# Power_Management.net
KiCad netlist of a schematic drawn in Altium Designer
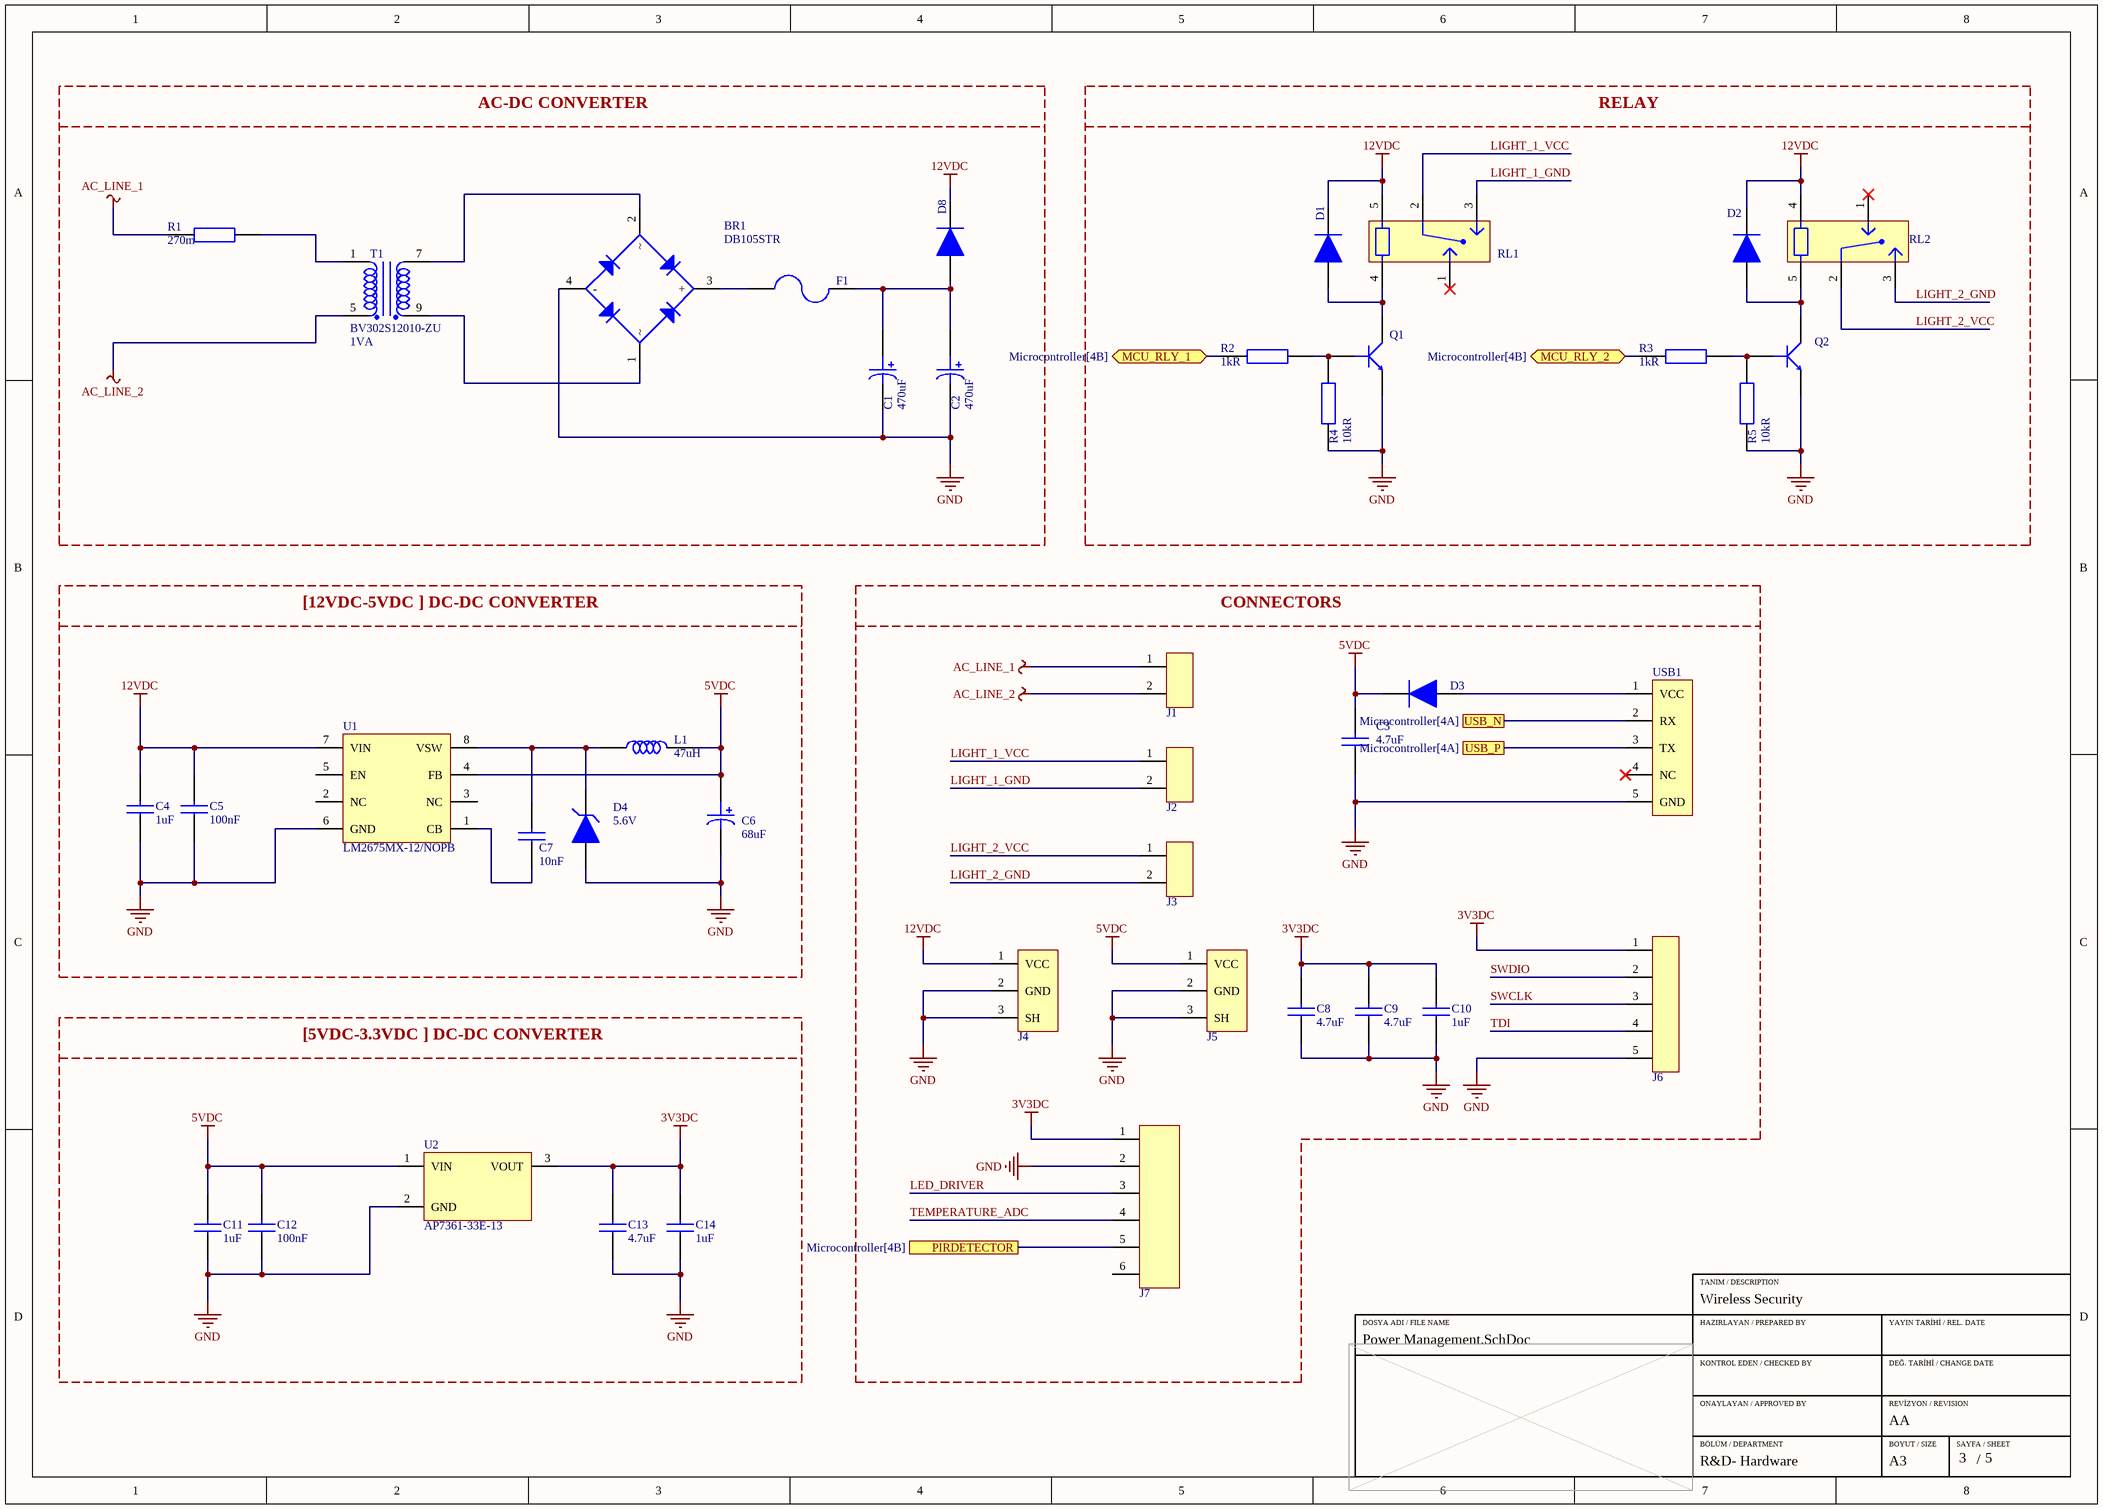
[diagram p0: Power Management.SchDoc]

(export (version "E")
  (design (tool "Eeschema 10.0.6"))
  (components
    (comp (ref "BR1")
      (value "DB105STR")
      (footprint "DB105STR")
      (description "Bridge Diode AC-DC")
      (fields
        (field (name "MANUFACTURER") "Sangdest Microelectronics")
        (field (name "DESIGNED BY") "Cem Uğurcan Özdemir")
      )
      (libsource (lib "UDEMY_Library") (part "DB105STR"))
    )
    (comp (ref "C1")
      (value "ESH477M050AH4AA")
      (footprint "CAP_RADIAL_D10_P5")
      (description "CAP ALU ELEC 470uF 50V RADIAL")
      (fields
        (field (name "MANUFACTURER") "KEMET")
        (field (name "TOLERANCE") "20%")
        (field (name "CAPACITANCE") "470uF")
        (field (name "DESIGNED BY") "Cem Uğurcan Özdemir")
      )
      (libsource (lib "UDEMY_Library") (part "CAP ALU ELEC 470uF 50V"))
    )
    (comp (ref "C2")
      (value "ESH477M050AH4AA")
      (footprint "CAP_RADIAL_D10_P5")
      (description "CAP ALU ELEC 470uF 50V RADIAL")
      (fields
        (field (name "MANUFACTURER") "KEMET")
        (field (name "TOLERANCE") "20%")
        (field (name "CAPACITANCE") "470uF")
        (field (name "DESIGNED BY") "Cem Uğurcan Özdemir")
      )
      (libsource (lib "UDEMY_Library") (part "CAP ALU ELEC 470uF 50V"))
    )
    (comp (ref "C3")
      (value "CL21A475KAQNNNE")
      (footprint "CAP_0805")
      (description "CAP CER 4.7uF %10 0805")
      (fields
        (field (name "MANUFACTURER") "Samsung")
        (field (name "TOLERANCE") "10%")
        (field (name "CAPACITANCE") "4.7uF")
        (field (name "DESIGNED BY") "Cem Uğurcan Özdemir")
      )
      (libsource (lib "UDEMY_Library") (part "CAP CER 4.7uF 0805"))
    )
    (comp (ref "C4")
      (value "CL21B105KBFNNNE")
      (footprint "CAP_0805")
      (description "CAP CER 1uF %10 0805")
      (fields
        (field (name "MANUFACTURER") "Samsung")
        (field (name "TOLERANCE") "10%")
        (field (name "CAPACITANCE") "1uF")
        (field (name "DESIGNED BY") "Cem Uğurcan Özdemir")
      )
      (libsource (lib "UDEMY_Library") (part "CAP CER 1uF 0805"))
    )
    (comp (ref "C5")
      (value "CL21B104KBCNNNC")
      (footprint "CAP_0805")
      (description "CAP CER 100nF %10 0805")
      (fields
        (field (name "MANUFACTURER") "Samsung")
        (field (name "TOLERANCE") "10%")
        (field (name "CAPACITANCE") "100nF")
        (field (name "DESIGNED BY") "Cem Uğurcan Özdemir")
      )
      (libsource (lib "UDEMY_Library") (part "CAP CER 100nF 0805"))
    )
    (comp (ref "C6")
      (value "EEV686M035A9HAA")
      (footprint "CAP_EEVseries")
      (description "Cap Aluminum Lytic 68uF 35V 20% (6.3 X 7.7mm) SMD 280mA 2000h 105C T/R")
      (fields
        (field (name "MANUFACTURER") "KEMET")
        (field (name "TOLERANCE") "20%")
        (field (name "CAPACITANCE") "68uF")
        (field (name "DESIGNED BY") "Cem Uğurcan Özdemir")
      )
      (libsource (lib "UDEMY_Library") (part "CAP ALU 68uF"))
    )
    (comp (ref "C7")
      (value "0603B103K160CT")
      (footprint "CAP_0603")
      (description "CAP CER 10nF %10 0603")
      (fields
        (field (name "MANUFACTURER") "Walsin Technologies")
        (field (name "TOLERANCE") "10%")
        (field (name "CAPACITANCE") "10nF")
        (field (name "DESIGNED BY") "Cem Uğurcan Özdemir")
      )
      (libsource (lib "UDEMY_Library") (part "CAP CER 10nF 0603"))
    )
    (comp (ref "C8")
      (value "CL21A475KAQNNNE")
      (footprint "CAP_0805")
      (description "CAP CER 4.7uF %10 0805")
      (fields
        (field (name "MANUFACTURER") "Samsung")
        (field (name "TOLERANCE") "10%")
        (field (name "CAPACITANCE") "4.7uF")
        (field (name "DESIGNED BY") "Cem Uğurcan Özdemir")
      )
      (libsource (lib "UDEMY_Library") (part "CAP CER 4.7uF 0805"))
    )
    (comp (ref "C9")
      (value "CL21A475KAQNNNE")
      (footprint "CAP_0805")
      (description "CAP CER 4.7uF %10 0805")
      (fields
        (field (name "MANUFACTURER") "Samsung")
        (field (name "TOLERANCE") "10%")
        (field (name "CAPACITANCE") "4.7uF")
        (field (name "DESIGNED BY") "Cem Uğurcan Özdemir")
      )
      (libsource (lib "UDEMY_Library") (part "CAP CER 4.7uF 0805"))
    )
    (comp (ref "C10")
      (value "CL21B105KBFNNNE")
      (footprint "CAP_0805")
      (description "CAP CER 1uF %10 0805")
      (fields
        (field (name "MANUFACTURER") "Samsung")
        (field (name "TOLERANCE") "10%")
        (field (name "CAPACITANCE") "1uF")
        (field (name "DESIGNED BY") "Cem Uğurcan Özdemir")
      )
      (libsource (lib "UDEMY_Library") (part "CAP CER 1uF 0805"))
    )
    (comp (ref "C11")
      (value "CL21B105KBFNNNE")
      (footprint "CAP_0805")
      (description "CAP CER 1uF %10 0805")
      (fields
        (field (name "MANUFACTURER") "Samsung")
        (field (name "TOLERANCE") "10%")
        (field (name "CAPACITANCE") "1uF")
        (field (name "DESIGNED BY") "Cem Uğurcan Özdemir")
      )
      (libsource (lib "UDEMY_Library") (part "CAP CER 1uF 0805"))
    )
    (comp (ref "C12")
      (value "C0603C104K5RACTU")
      (footprint "CAP_0603")
      (description "CAP CER 100nF %10 0603 SMD")
      (fields
        (field (name "MANUFACTURER") "KEMET")
        (field (name "TOLERANCE") "10%")
        (field (name "CAPACITANCE") "100nF")
        (field (name "DESIGNED BY") "Cem Uğurcan Özdemir")
      )
      (libsource (lib "UDEMY_Library") (part "CAP CER 100nF 0603"))
    )
    (comp (ref "C13")
      (value "CL21A475KAQNNNE")
      (footprint "CAP_0805")
      (description "CAP CER 4.7uF %10 0805")
      (fields
        (field (name "MANUFACTURER") "Samsung")
        (field (name "TOLERANCE") "10%")
        (field (name "CAPACITANCE") "4.7uF")
        (field (name "DESIGNED BY") "Cem Uğurcan Özdemir")
      )
      (libsource (lib "UDEMY_Library") (part "CAP CER 4.7uF 0805"))
    )
    (comp (ref "C14")
      (value "CL21B105KBFNNNE")
      (footprint "CAP_0805")
      (description "CAP CER 1uF %10 0805")
      (fields
        (field (name "MANUFACTURER") "Samsung")
        (field (name "TOLERANCE") "10%")
        (field (name "CAPACITANCE") "1uF")
        (field (name "DESIGNED BY") "Cem Uğurcan Özdemir")
      )
      (libsource (lib "UDEMY_Library") (part "CAP CER 1uF 0805"))
    )
    (comp (ref "D1")
      (value "1N4148WS")
      (footprint "SOD323F")
      (description "Diode, Single, 75 V, 150 mA, 1 V, 4 ns")
      (fields
        (field (name "MANUFACTURER") "ON Semiconductor / Fairchild")
        (field (name "DESIGNED BY") "Cem Uğurcan Özdemir")
      )
      (libsource (lib "UDEMY_Library") (part "1N4148WS"))
    )
    (comp (ref "D2")
      (value "1N4148WS")
      (footprint "SOD323F")
      (description "Diode, Single, 75 V, 150 mA, 1 V, 4 ns")
      (fields
        (field (name "MANUFACTURER") "ON Semiconductor / Fairchild")
        (field (name "DESIGNED BY") "Cem Uğurcan Özdemir")
      )
      (libsource (lib "UDEMY_Library") (part "1N4148WS"))
    )
    (comp (ref "D3")
      (value "1N4148WS")
      (footprint "SOD323F")
      (description "Diode, Single, 75 V, 150 mA, 1 V, 4 ns")
      (fields
        (field (name "MANUFACTURER") "ON Semiconductor / Fairchild")
        (field (name "DESIGNED BY") "Cem Uğurcan Özdemir")
      )
      (libsource (lib "UDEMY_Library") (part "1N4148WS"))
    )
    (comp (ref "D4")
      (value "1SMB5919BT3G")
      (footprint "SMB")
      (description "Diode Zener Single 5.6V 5% 3W 2-Pin SMB T/R")
      (fields
        (field (name "MANUFACTURER") "ON Semiconductor")
        (field (name "TOLERANCE") "5%")
        (field (name "WORKING VOLTAGE") "5.6V")
        (field (name "DESIGNED BY") "Cem Uğurcan Özdemir")
      )
      (libsource (lib "UDEMY_Library") (part "1SMB5919BT3G"))
    )
    (comp (ref "D8")
      (value "1N4148WS")
      (footprint "SOD323F")
      (description "Diode, Single, 75 V, 150 mA, 1 V, 4 ns")
      (fields
        (field (name "MANUFACTURER") "ON Semiconductor / Fairchild")
        (field (name "DESIGNED BY") "Cem Uğurcan Özdemir")
      )
      (libsource (lib "UDEMY_Library") (part "1N4148WS"))
    )
    (comp (ref "F1")
      (value "3413.0216.22")
      (footprint "3413.0216.22")
      (description "FUSE BRD MNT 1A 32VAC 63VDC 1206")
      (fields (field (name "MANUFACTURER") "Schurter") (field (name "DESIGNED BY") "Cem Uğurcan Özdemir"))
      (libsource (lib "UDEMY_Library") (part "FUSE 3413.0216.22"))
    )
    (comp (ref "J1")
      (value "TBP01R1-508-02BE")
      (footprint "TBP01R1-508")
      (description "Conn Shrouded Header HDR 2 POS 5.08mm Solder RA Side Entry Thru-Hole Bag")
      (fields (field (name "MANUFACTURER") "CUI") (field (name "DESIGNED BY") "Cem Uğurcan Özdemir"))
      (libsource (lib "UDEMY_Library") (part "TBP01R1-508-02BE"))
    )
    (comp (ref "J2")
      (value "TBP01R1-508-02BE")
      (footprint "TBP01R1-508")
      (description "Conn Shrouded Header HDR 2 POS 5.08mm Solder RA Side Entry Thru-Hole Bag")
      (fields (field (name "MANUFACTURER") "CUI") (field (name "DESIGNED BY") "Cem Uğurcan Özdemir"))
      (libsource (lib "UDEMY_Library") (part "TBP01R1-508-02BE"))
    )
    (comp (ref "J3")
      (value "TBP01R1-508-02BE")
      (footprint "TBP01R1-508")
      (description "Conn Shrouded Header HDR 2 POS 5.08mm Solder RA Side Entry Thru-Hole Bag")
      (fields (field (name "MANUFACTURER") "CUI") (field (name "DESIGNED BY") "Cem Uğurcan Özdemir"))
      (libsource (lib "UDEMY_Library") (part "TBP01R1-508-02BE"))
    )
    (comp (ref "J4")
      (value "PJ-037AH-SMT-TR")
      (footprint "JACK")
      (description "DC Power Connectors Power Jacks")
      (fields (field (name "MANUFACTURER") "CUI") (field (name "DESIGNED BY") "Cem Uğurcan Özdemir"))
      (libsource (lib "UDEMY_Library") (part "PJ-037AH-SMT-TR"))
    )
    (comp (ref "J5")
      (value "PJ-037AH-SMT-TR")
      (footprint "JACK")
      (description "DC Power Connectors Power Jacks")
      (fields (field (name "MANUFACTURER") "CUI") (field (name "DESIGNED BY") "Cem Uğurcan Özdemir"))
      (libsource (lib "UDEMY_Library") (part "PJ-037AH-SMT-TR"))
    )
    (comp (ref "J6")
      (value "SMH-105-02-L-S")
      (footprint "PINHEADER1X5_RA")
      (description ".100 C.L. HORIZONTAL SMT SOCKET")
      (fields (field (name "MANUFACTURER") "Samtec") (field (name "DESIGNED BY") "Cem Uğurcan Özdemir"))
      (libsource (lib "UDEMY_Library") (part "SMH-105-02-L-S"))
    )
    (comp (ref "J7")
      (value "64800611622")
      (footprint "64800611622")
      (description "1.50mm 6PIN Connector")
      (fields
        (field (name "MANUFACTURER") "Wurth Electronics")
        (field (name "DESIGNED BY") "Cem Uğurcan Özdemir")
      )
      (libsource (lib "UDEMY_Library") (part "64800611622_conn_6pin"))
    )
    (comp (ref "L1")
      (value "78438335470")
      (footprint "IND_1212")
      (description "FIXED IND 47UH 390MA 2.3 OHM SMD")
      (fields
        (field (name "MANUFACTURER") "Wurth Electronics")
        (field (name "TOLERANCE") "30%")
        (field (name "INDUCTANCE") "47uH")
        (field (name "DESIGNED BY") "Cem Uğurcan Özdemir")
      )
      (libsource (lib "UDEMY_Library") (part "IND 47uH"))
    )
    (comp (ref "Q1")
      (value "MMBT3904-7-F")
      (footprint "SOT-23F")
      (description "Transistor General Purpose BJT NPN 40 Volt 0.2A Automotive 3-Pin SOT-23")
      (fields (field (name "MANUFACTURER") "Diodes Zetex") (field (name "DESIGNED BY") "Cem Uğurcan Özdemir"))
      (libsource (lib "UDEMY_Library") (part "MMBT3904-7-F"))
    )
    (comp (ref "Q2")
      (value "MMBT3904-7-F")
      (footprint "SOT-23F")
      (description "Transistor General Purpose BJT NPN 40 Volt 0.2A Automotive 3-Pin SOT-23")
      (fields (field (name "MANUFACTURER") "Diodes Zetex") (field (name "DESIGNED BY") "Cem Uğurcan Özdemir"))
      (libsource (lib "UDEMY_Library") (part "MMBT3904-7-F"))
    )
    (comp (ref "R1")
      (value "5WD27")
      (footprint "RES_AXIAL_W")
      (description "Resistor 5 Watt Cermet Wirewound Flameproof .27 Ohm 5% Axial Lead")
      (fields
        (field (name "MANUFACTURER") "NTE Electronics")
        (field (name "TOLERANCE") "5%")
        (field (name "RESISTANCE") "270m")
        (field (name "DESIGNED BY") "Cem Uğurcan Özdemir")
      )
      (libsource (lib "CourseProjectLibrary") (part "5WD27"))
    )
    (comp (ref "R2")
      (value "RC0603FR-0710KL")
      (footprint "RES_0603")
      (description "RES 1K %1 OHM 0603 SMD")
      (fields
        (field (name "MANUFACTURER") "Yageo")
        (field (name "MANUFACTURER PART NUMBER") "RC0603JR-071KL")
        (field (name "RESISTANCE") "1kR")
        (field (name "DESIGNED BY") "Cem Uğurcan Özdemir")
      )
      (libsource (lib "UDEMY_Library") (part "RES 1K OHM 0603"))
    )
    (comp (ref "R3")
      (value "RC0603FR-0710KL")
      (footprint "RES_0603")
      (description "RES 1K %1 OHM 0603 SMD")
      (fields
        (field (name "MANUFACTURER") "Yageo")
        (field (name "MANUFACTURER PART NUMBER") "RC0603JR-071KL")
        (field (name "RESISTANCE") "1kR")
        (field (name "DESIGNED BY") "Cem Uğurcan Özdemir")
      )
      (libsource (lib "UDEMY_Library") (part "RES 1K OHM 0603"))
    )
    (comp (ref "R4")
      (value "RC0603FR-0710KL")
      (footprint "RES_0603")
      (description "RES 10K %1 OHM 0603 SMD")
      (fields
        (field (name "MANUFACTURER") "Yageo")
        (field (name "TOLERANCE") "1%")
        (field (name "RESISTANCE") "10kR")
        (field (name "DESIGNED BY") "Cem Uğurcan Özdemir")
      )
      (libsource (lib "UDEMY_Library") (part "RES 10K OHM 0603"))
    )
    (comp (ref "R5")
      (value "RC0603FR-0710KL")
      (footprint "RES_0603")
      (description "RES 10K %1 OHM 0603 SMD")
      (fields
        (field (name "MANUFACTURER") "Yageo")
        (field (name "TOLERANCE") "1%")
        (field (name "RESISTANCE") "10kR")
        (field (name "DESIGNED BY") "Cem Uğurcan Özdemir")
      )
      (libsource (lib "UDEMY_Library") (part "RES 10K OHM 0603"))
    )
    (comp (ref "RL1")
      (value "ALQ112")
      (footprint "ALQ112")
      (description "General Purpose Relay SPDT (1 Form C) 12VDC Coil Through Hole")
      (fields (field (name "MANUFACTURER") "Panasonic") (field (name "DESIGNED BY") "Cem Uğurcan Özdemir"))
      (libsource (lib "UDEMY_Library") (part "ALQ112"))
    )
    (comp (ref "RL2")
      (value "ALQ112")
      (footprint "ALQ112")
      (description "General Purpose Relay SPDT (1 Form C) 12VDC Coil Through Hole")
      (fields (field (name "MANUFACTURER") "Panasonic") (field (name "DESIGNED BY") "Cem Uğurcan Özdemir"))
      (libsource (lib "") (part "ALQ112_1"))
    )
    (comp (ref "T1")
      (value "BV302S12010-ZU")
      (footprint "BV302S")
      (description "230-12 Transformer 1VA")
      (fields
        (field (name "MANUFACTURER") "Zettler Magnetics")
        (field (name "RATED POWER") "1VA")
        (field (name "DESIGNED BY") "Cem Uğurcan Özdemir")
      )
      (libsource (lib "UDEMY_Library") (part "BV302S12010-ZU"))
    )
    (comp (ref "U1")
      (value "LM2675MX-12/NOPB")
      (footprint "SOIC8")
      (description "Switching Voltage Regulators Pwr Cnvtr Hi Eff 1A SD Vtg Reg")
      (fields
        (field (name "MANUFACTURER") "TI National Semiconductor")
        (field (name "DESIGNED BY") "Cem Uğurcan Özdemir")
      )
      (libsource (lib "UDEMY_Library") (part "LM2675MX-12/NOPB"))
    )
    (comp (ref "U2")
      (value "AP7361-33E-13")
      (footprint "SOT223")
      (description "LDO Regulator Pos 3.3V 1A 4-Pin(3+Tab) SOT-223 T/R")
      (fields (field (name "MANUFACTURER") "Diodes") (field (name "DESIGNED BY") "Cem Uğurcan Özdemir"))
      (libsource (lib "UDEMY_Library") (part "AP7361-33E-13"))
    )
    (comp (ref "USB1")
      (value "10118192-0001LF")
      (footprint "MICRO_B_USB")
      (description "CONN RCPT USB2.0 MICRO B SMD R/A")
      (fields (field (name "MANUFACTURER") "Amphenol FCI") (field (name "DESIGNED BY") "Cem Uğurcan Özdemir"))
      (libsource (lib "UDEMY_Library") (part "Micro B USB Connector"))
    )
  )
  (nets
    (net (code "1") (name "/LED_DRIVER") (class "Default") (node (ref "J7") (pin "3") (pintype "power_in")))
    (net (code "2") (name "/LIGHT_1_GND") (class "Default")
      (node (ref "J2") (pin "2") (pinfunction "2_2") (pintype "power_in"))
      (node (ref "RL1") (pin "3") (pinfunction "3_3") (pintype "passive"))
    )
    (net (code "3") (name "/LIGHT_1_VCC") (class "Default")
      (node (ref "J2") (pin "1") (pinfunction "1_1") (pintype "power_in"))
      (node (ref "RL1") (pin "2") (pinfunction "2_2") (pintype "passive"))
    )
    (net (code "4") (name "/LIGHT_2_GND") (class "Default")
      (node (ref "J3") (pin "2") (pinfunction "2_2") (pintype "power_in"))
      (node (ref "RL2") (pin "3") (pinfunction "3_3") (pintype "passive"))
    )
    (net (code "5") (name "/LIGHT_2_VCC") (class "Default")
      (node (ref "J3") (pin "1") (pinfunction "1_1") (pintype "power_in"))
      (node (ref "RL2") (pin "2") (pinfunction "2_2") (pintype "passive"))
    )
    (net (code "6") (name "/MCU_RLY_1") (class "Default")
      (node (ref "R2") (pin "1") (pinfunction "1_1") (pintype "passive"))
    )
    (net (code "7") (name "/MCU_RLY_2") (class "Default")
      (node (ref "R3") (pin "1") (pinfunction "1_1") (pintype "passive"))
    )
    (net (code "8") (name "/PIRDETECTOR") (class "Default") (node (ref "J7") (pin "5") (pintype "power_in")))
    (net (code "9") (name "/SWCLK") (class "Default")
      (node (ref "J6") (pin "3") (pinfunction "3_3") (pintype "power_in"))
    )
    (net (code "10") (name "/SWDIO") (class "Default")
      (node (ref "J6") (pin "2") (pinfunction "2_2") (pintype "power_in"))
    )
    (net (code "11") (name "/TDI") (class "Default")
      (node (ref "J6") (pin "4") (pinfunction "4_4") (pintype "power_in"))
    )
    (net (code "12") (name "/TEMPERATURE_ADC") (class "Default")
      (node (ref "J7") (pin "4") (pintype "power_in"))
    )
    (net (code "13") (name "/USB_N") (class "Default")
      (node (ref "USB1") (pin "2") (pinfunction "RX_2") (pintype "power_in"))
    )
    (net (code "14") (name "/USB_P") (class "Default")
      (node (ref "USB1") (pin "3") (pinfunction "TX_3") (pintype "power_in"))
    )
    (net (code "15") (name "3V3DC") (class "Default")
      (node (ref "C10") (pin "2") (pinfunction "2_2") (pintype "passive"))
      (node (ref "C13") (pin "2") (pinfunction "2_2") (pintype "passive"))
      (node (ref "C14") (pin "2") (pinfunction "2_2") (pintype "passive"))
      (node (ref "C8") (pin "2") (pinfunction "2_2") (pintype "passive"))
      (node (ref "C9") (pin "2") (pinfunction "2_2") (pintype "passive"))
      (node (ref "J6") (pin "1") (pinfunction "1_1") (pintype "power_in"))
      (node (ref "J7") (pin "1") (pintype "power_in"))
      (node (ref "U2") (pin "3") (pinfunction "VOUT_3") (pintype "passive"))
    )
    (net (code "16") (name "5VDC") (class "Default")
      (node (ref "C11") (pin "2") (pinfunction "2_2") (pintype "passive"))
      (node (ref "C12") (pin "2") (pinfunction "2_2") (pintype "passive"))
      (node (ref "C3") (pin "2") (pinfunction "2_2") (pintype "passive"))
      (node (ref "C6") (pin "1") (pinfunction "1_1") (pintype "passive"))
      (node (ref "D3") (pin "1") (pinfunction "1_1") (pintype "power_in"))
      (node (ref "J5") (pin "1") (pinfunction "VCC_1") (pintype "power_in"))
      (node (ref "L1") (pin "2") (pinfunction "2_2") (pintype "passive"))
      (node (ref "U1") (pin "4") (pinfunction "FB_4") (pintype "passive"))
      (node (ref "U2") (pin "1") (pinfunction "VIN_1") (pintype "passive"))
    )
    (net (code "17") (name "12VDC") (class "Default")
      (node (ref "C4") (pin "2") (pinfunction "2_2") (pintype "passive"))
      (node (ref "C5") (pin "2") (pinfunction "2_2") (pintype "passive"))
      (node (ref "D1") (pin "1") (pinfunction "1_1") (pintype "power_in"))
      (node (ref "D2") (pin "1") (pinfunction "1_1") (pintype "power_in"))
      (node (ref "D8") (pin "1") (pinfunction "1_1") (pintype "power_in"))
      (node (ref "J4") (pin "1") (pinfunction "VCC_1") (pintype "power_in"))
      (node (ref "RL1") (pin "5") (pinfunction "5_5") (pintype "passive"))
      (node (ref "RL2") (pin "4") (pinfunction "4_4") (pintype "passive"))
      (node (ref "U1") (pin "7") (pinfunction "VIN_7") (pintype "passive"))
    )
    (net (code "18") (name "AC_LINE_1") (class "Default")
      (node (ref "J1") (pin "1") (pinfunction "1_1") (pintype "power_in"))
      (node (ref "R1") (pin "1") (pinfunction "1_1") (pintype "passive"))
    )
    (net (code "19") (name "AC_LINE_2") (class "Default")
      (node (ref "J1") (pin "2") (pinfunction "2_2") (pintype "power_in"))
      (node (ref "T1") (pin "5") (pinfunction "5_5") (pintype "passive"))
    )
    (net (code "20") (name "GND") (class "Default")
      (node (ref "BR1") (pin "4") (pinfunction "-_4") (pintype "passive"))
      (node (ref "C1") (pin "2") (pinfunction "2_2") (pintype "passive"))
      (node (ref "C10") (pin "1") (pinfunction "1_1") (pintype "passive"))
      (node (ref "C11") (pin "1") (pinfunction "1_1") (pintype "passive"))
      (node (ref "C12") (pin "1") (pinfunction "1_1") (pintype "passive"))
      (node (ref "C13") (pin "1") (pinfunction "1_1") (pintype "passive"))
      (node (ref "C14") (pin "1") (pinfunction "1_1") (pintype "passive"))
      (node (ref "C2") (pin "2") (pinfunction "2_2") (pintype "passive"))
      (node (ref "C3") (pin "1") (pinfunction "1_1") (pintype "passive"))
      (node (ref "C4") (pin "1") (pinfunction "1_1") (pintype "passive"))
      (node (ref "C5") (pin "1") (pinfunction "1_1") (pintype "passive"))
      (node (ref "C6") (pin "2") (pinfunction "2_2") (pintype "passive"))
      (node (ref "C8") (pin "1") (pinfunction "1_1") (pintype "passive"))
      (node (ref "C9") (pin "1") (pinfunction "1_1") (pintype "passive"))
      (node (ref "D4") (pin "A") (pinfunction "A_A") (pintype "passive"))
      (node (ref "J4") (pin "2") (pinfunction "GND_2") (pintype "power_in"))
      (node (ref "J4") (pin "3") (pinfunction "SH_3") (pintype "power_in"))
      (node (ref "J5") (pin "2") (pinfunction "GND_2") (pintype "power_in"))
      (node (ref "J5") (pin "3") (pinfunction "SH_3") (pintype "power_in"))
      (node (ref "J6") (pin "5") (pinfunction "5_5") (pintype "power_in"))
      (node (ref "J7") (pin "2") (pintype "power_in"))
      (node (ref "Q1") (pin "2") (pinfunction "E_2") (pintype "power_in"))
      (node (ref "Q2") (pin "2") (pinfunction "E_2") (pintype "power_in"))
      (node (ref "R4") (pin "1") (pinfunction "1_1") (pintype "passive"))
      (node (ref "R5") (pin "1") (pinfunction "1_1") (pintype "passive"))
      (node (ref "U1") (pin "6") (pinfunction "GND_6") (pintype "passive"))
      (node (ref "U2") (pin "2") (pinfunction "GND_2") (pintype "passive"))
      (node (ref "USB1") (pin "5") (pinfunction "GND_5") (pintype "power_in"))
    )
    (net (code "21") (name "Net-(BR1-+)") (class "Default")
      (node (ref "BR1") (pin "3") (pinfunction "+_3") (pintype "passive"))
      (node (ref "F1") (pin "1") (pinfunction "1_1") (pintype "passive"))
    )
    (net (code "22") (name "Net-(BR1-~-Pad1)") (class "Default")
      (node (ref "BR1") (pin "1") (pinfunction "~_1") (pintype "passive"))
      (node (ref "T1") (pin "9") (pinfunction "9_9") (pintype "passive"))
    )
    (net (code "23") (name "Net-(BR1-~-Pad2)") (class "Default")
      (node (ref "BR1") (pin "2") (pinfunction "~_2") (pintype "passive"))
      (node (ref "T1") (pin "7") (pinfunction "7_7") (pintype "passive"))
    )
    (net (code "24") (name "Net-(C1-Pad1)") (class "Default")
      (node (ref "C1") (pin "1") (pinfunction "1_1") (pintype "passive"))
      (node (ref "C2") (pin "1") (pinfunction "1_1") (pintype "passive"))
      (node (ref "D8") (pin "2") (pinfunction "2_2") (pintype "power_in"))
      (node (ref "F1") (pin "2") (pinfunction "2_2") (pintype "passive"))
    )
    (net (code "25") (name "Net-(Q1-B)") (class "Default")
      (node (ref "Q1") (pin "1") (pinfunction "B_1") (pintype "power_in"))
      (node (ref "R2") (pin "2") (pinfunction "2_2") (pintype "passive"))
      (node (ref "R4") (pin "2") (pinfunction "2_2") (pintype "passive"))
    )
    (net (code "26") (name "Net-(Q1-C)") (class "Default")
      (node (ref "D1") (pin "2") (pinfunction "2_2") (pintype "power_in"))
      (node (ref "Q1") (pin "3") (pinfunction "C_3") (pintype "power_in"))
      (node (ref "RL1") (pin "4") (pinfunction "4_4") (pintype "passive"))
    )
    (net (code "27") (name "Net-(Q2-B)") (class "Default")
      (node (ref "Q2") (pin "1") (pinfunction "B_1") (pintype "power_in"))
      (node (ref "R3") (pin "2") (pinfunction "2_2") (pintype "passive"))
      (node (ref "R5") (pin "2") (pinfunction "2_2") (pintype "passive"))
    )
    (net (code "28") (name "Net-(Q2-C)") (class "Default")
      (node (ref "D2") (pin "2") (pinfunction "2_2") (pintype "power_in"))
      (node (ref "Q2") (pin "3") (pinfunction "C_3") (pintype "power_in"))
      (node (ref "RL2") (pin "5") (pinfunction "5_5") (pintype "passive"))
    )
    (net (code "29") (name "Net-(R1-Pad2)") (class "Default")
      (node (ref "R1") (pin "2") (pinfunction "2_2") (pintype "passive"))
      (node (ref "T1") (pin "1") (pinfunction "1_1") (pintype "passive"))
    )
    (net (code "30") (name "Net-(U1-CB)") (class "Default")
      (node (ref "C7") (pin "1") (pinfunction "1_1") (pintype "passive"))
      (node (ref "U1") (pin "1") (pinfunction "CB_1") (pintype "passive"))
    )
    (net (code "31") (name "Net-(U1-VSW)") (class "Default")
      (node (ref "C7") (pin "2") (pinfunction "2_2") (pintype "passive"))
      (node (ref "D4") (pin "C") (pinfunction "C_C") (pintype "passive"))
      (node (ref "L1") (pin "1") (pinfunction "1_1") (pintype "passive"))
      (node (ref "U1") (pin "8") (pinfunction "VSW_8") (pintype "passive"))
    )
    (net (code "32") (name "Net-(USB1-VCC)") (class "Default")
      (node (ref "D3") (pin "2") (pinfunction "2_2") (pintype "power_in"))
      (node (ref "USB1") (pin "1") (pinfunction "VCC_1") (pintype "power_in"))
    )
    (net (code "33") (name "unconnected-(J7-Pad6)") (class "Default")
      (node (ref "J7") (pin "6") (pintype "power_in"))
    )
    (net (code "34") (name "unconnected-(RL1-Pad1)") (class "Default")
      (node (ref "RL1") (pin "1") (pinfunction "1_1") (pintype "passive+no_connect"))
    )
    (net (code "35") (name "unconnected-(RL2-Pad1)") (class "Default")
      (node (ref "RL2") (pin "1") (pinfunction "1_1") (pintype "passive+no_connect"))
    )
    (net (code "36") (name "unconnected-(U1-EN-Pad5)") (class "Default")
      (node (ref "U1") (pin "5") (pinfunction "EN_5") (pintype "passive"))
    )
    (net (code "37") (name "unconnected-(U1-NC-Pad2)") (class "Default")
      (node (ref "U1") (pin "2") (pinfunction "NC_2") (pintype "passive"))
    )
    (net (code "38") (name "unconnected-(U1-NC-Pad3)") (class "Default")
      (node (ref "U1") (pin "3") (pinfunction "NC_3") (pintype "passive"))
    )
    (net (code "39") (name "unconnected-(USB1-NC-Pad4)") (class "Default")
      (node (ref "USB1") (pin "4") (pinfunction "NC_4") (pintype "power_in+no_connect"))
    )
  )
)
